# 06_FPGA_B.net
KiCad netlist of a schematic drawn in Altium Designer
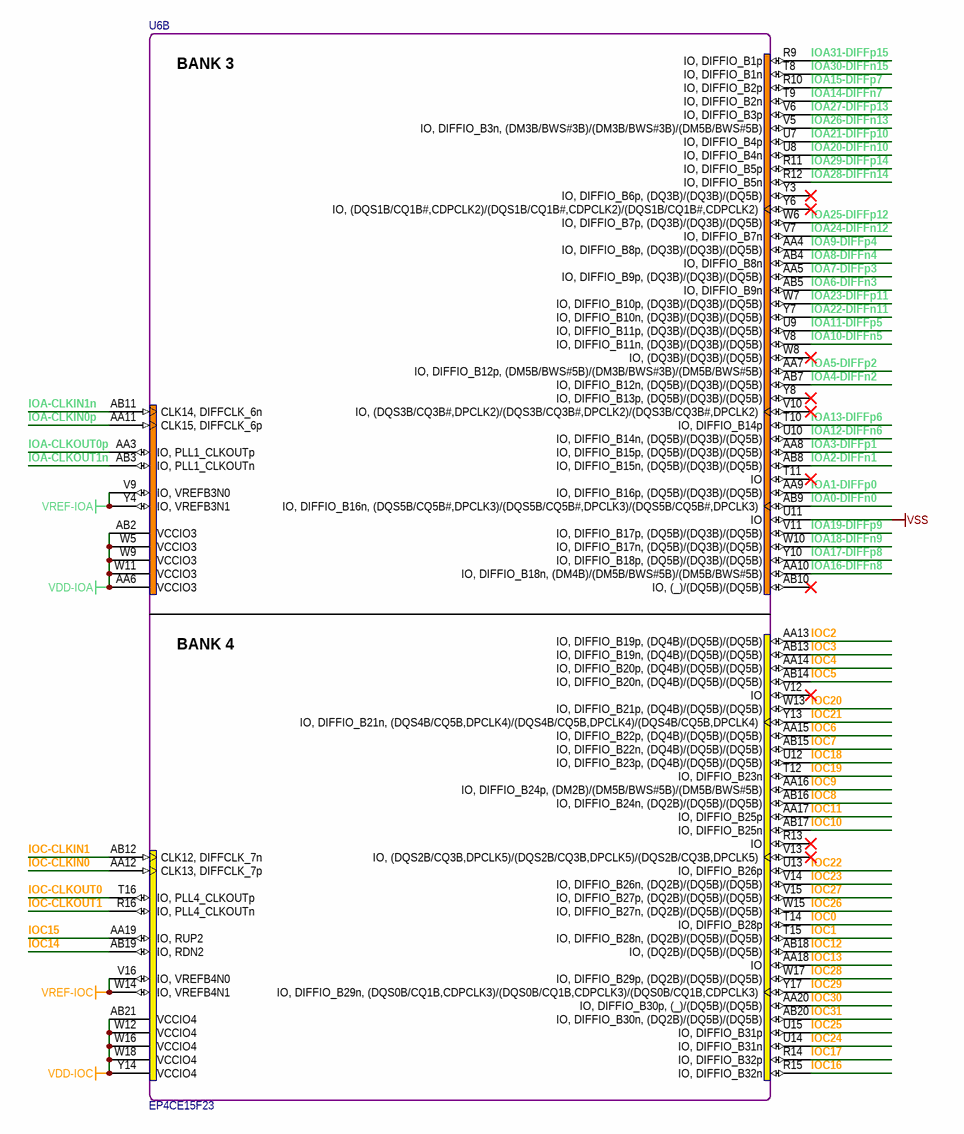
[diagram p0: 06_FPGA_B.SchDoc]

(export (version "E")
  (design (tool "Eeschema 10.0.6"))
  (components
    (comp (ref "U6")
      (value "EP4CE15F23")
      (footprint "FBGA-484")
      (description "Cyclone IV EP4CE15F23 FPGA")
      (fields
        (field (name "PARTNUMBER") "EP4CE15F23C8N")
        (field (name "DESIGNER") "shyul")
        (field (name "PUBLISHER") "Cowin")
      )
      (libsource (lib "PCB_XEM-S91") (part "EP4CE15F23"))
    )
  )
  (nets
    (net (code "1") (name "/IOA-CLKIN0p") (class "Default")
      (node (ref "U6") (pin "AA11") (pinfunction "CLK15,_DIFFCLK_6p_AA11") (pintype "input"))
    )
    (net (code "2") (name "/IOA-CLKIN1n") (class "Default")
      (node (ref "U6") (pin "AB11") (pinfunction "CLK14,_DIFFCLK_6n_AB11") (pintype "input"))
    )
    (net (code "3") (name "/IOA-CLKOUT0p") (class "Default")
      (node (ref "U6") (pin "AA3") (pinfunction "IO,_PLL1_CLKOUTp_AA3") (pintype "bidirectional"))
    )
    (net (code "4") (name "/IOA-CLKOUT1n") (class "Default")
      (node (ref "U6") (pin "AB3") (pinfunction "IO,_PLL1_CLKOUTn_AB3") (pintype "bidirectional"))
    )
    (net (code "5") (name "/IOA0-DIFFn0") (class "Default")
      (node (ref "U6") (pin "AB9") (pinfunction "IO,_DIFFIO_B16n,_(DQS5B/CQ5B#,DPCLK3)/(DQS5B/CQ5B#,DPCLK3)/(DQS5B/CQ5B#,DPCLK3)_AB9") (pintype "bidirectional"))
    )
    (net (code "6") (name "/IOA1-DIFFp0") (class "Default")
      (node (ref "U6") (pin "AA9") (pinfunction "IO,_DIFFIO_B16p,_(DQ5B)/(DQ3B)/(DQ5B)_AA9") (pintype "bidirectional"))
    )
    (net (code "7") (name "/IOA2-DIFFn1") (class "Default")
      (node (ref "U6") (pin "AB8") (pinfunction "IO,_DIFFIO_B15n,_(DQ5B)/(DQ3B)/(DQ5B)_AB8") (pintype "bidirectional"))
    )
    (net (code "8") (name "/IOA3-DIFFp1") (class "Default")
      (node (ref "U6") (pin "AA8") (pinfunction "IO,_DIFFIO_B15p,_(DQ5B)/(DQ3B)/(DQ5B)_AA8") (pintype "bidirectional"))
    )
    (net (code "9") (name "/IOA4-DIFFn2") (class "Default")
      (node (ref "U6") (pin "AB7") (pinfunction "IO,_DIFFIO_B12n,_(DQ5B)/(DQ3B)/(DQ5B)_AB7") (pintype "bidirectional"))
    )
    (net (code "10") (name "/IOA5-DIFFp2") (class "Default")
      (node (ref "U6") (pin "AA7") (pinfunction "IO,_DIFFIO_B12p,_(DM5B/BWS#5B)/(DM3B/BWS#3B)/(DM5B/BWS#5B)_AA7") (pintype "bidirectional"))
    )
    (net (code "11") (name "/IOA6-DIFFn3") (class "Default")
      (node (ref "U6") (pin "AB5") (pinfunction "IO,_DIFFIO_B9n_AB5") (pintype "bidirectional"))
    )
    (net (code "12") (name "/IOA7-DIFFp3") (class "Default")
      (node (ref "U6") (pin "AA5") (pinfunction "IO,_DIFFIO_B9p,_(DQ3B)/(DQ3B)/(DQ5B)_AA5") (pintype "bidirectional"))
    )
    (net (code "13") (name "/IOA8-DIFFn4") (class "Default")
      (node (ref "U6") (pin "AB4") (pinfunction "IO,_DIFFIO_B8n_AB4") (pintype "bidirectional"))
    )
    (net (code "14") (name "/IOA9-DIFFp4") (class "Default")
      (node (ref "U6") (pin "AA4") (pinfunction "IO,_DIFFIO_B8p,_(DQ3B)/(DQ3B)/(DQ5B)_AA4") (pintype "bidirectional"))
    )
    (net (code "15") (name "/IOA10-DIFFn5") (class "Default")
      (node (ref "U6") (pin "V8") (pinfunction "IO,_DIFFIO_B11n,_(DQ3B)/(DQ3B)/(DQ5B)_V8") (pintype "bidirectional"))
    )
    (net (code "16") (name "/IOA11-DIFFp5") (class "Default")
      (node (ref "U6") (pin "U9") (pinfunction "IO,_DIFFIO_B11p,_(DQ3B)/(DQ3B)/(DQ5B)_U9") (pintype "bidirectional"))
    )
    (net (code "17") (name "/IOA12-DIFFn6") (class "Default")
      (node (ref "U6") (pin "U10") (pinfunction "IO,_DIFFIO_B14n,_(DQ5B)/(DQ3B)/(DQ5B)_U10") (pintype "bidirectional"))
    )
    (net (code "18") (name "/IOA13-DIFFp6") (class "Default")
      (node (ref "U6") (pin "T10") (pinfunction "IO,_DIFFIO_B14p_T10") (pintype "bidirectional"))
    )
    (net (code "19") (name "/IOA14-DIFFn7") (class "Default")
      (node (ref "U6") (pin "T9") (pinfunction "IO,_DIFFIO_B2n_T9") (pintype "bidirectional"))
    )
    (net (code "20") (name "/IOA15-DIFFp7") (class "Default")
      (node (ref "U6") (pin "R10") (pinfunction "IO,_DIFFIO_B2p_R10") (pintype "bidirectional"))
    )
    (net (code "21") (name "/IOA16-DIFFn8") (class "Default")
      (node (ref "U6") (pin "AA10") (pinfunction "IO,_DIFFIO_B18n,_(DM4B)/(DM5B/BWS#5B)/(DM5B/BWS#5B)_AA10") (pintype "bidirectional"))
    )
    (net (code "22") (name "/IOA17-DIFFp8") (class "Default")
      (node (ref "U6") (pin "Y10") (pinfunction "IO,_DIFFIO_B18p,_(DQ5B)/(DQ3B)/(DQ5B)_Y10") (pintype "bidirectional"))
    )
    (net (code "23") (name "/IOA18-DIFFn9") (class "Default")
      (node (ref "U6") (pin "W10") (pinfunction "IO,_DIFFIO_B17n,_(DQ5B)/(DQ3B)/(DQ5B)_W10") (pintype "bidirectional"))
    )
    (net (code "24") (name "/IOA19-DIFFp9") (class "Default")
      (node (ref "U6") (pin "V11") (pinfunction "IO,_DIFFIO_B17p,_(DQ5B)/(DQ3B)/(DQ5B)_V11") (pintype "bidirectional"))
    )
    (net (code "25") (name "/IOA20-DIFFn10") (class "Default")
      (node (ref "U6") (pin "U8") (pinfunction "IO,_DIFFIO_B4n_U8") (pintype "bidirectional"))
    )
    (net (code "26") (name "/IOA21-DIFFp10") (class "Default")
      (node (ref "U6") (pin "U7") (pinfunction "IO,_DIFFIO_B4p_U7") (pintype "bidirectional"))
    )
    (net (code "27") (name "/IOA22-DIFFn11") (class "Default")
      (node (ref "U6") (pin "Y7") (pinfunction "IO,_DIFFIO_B10n,_(DQ3B)/(DQ3B)/(DQ5B)_Y7") (pintype "bidirectional"))
    )
    (net (code "28") (name "/IOA23-DIFFp11") (class "Default")
      (node (ref "U6") (pin "W7") (pinfunction "IO,_DIFFIO_B10p,_(DQ3B)/(DQ3B)/(DQ5B)_W7") (pintype "bidirectional"))
    )
    (net (code "29") (name "/IOA24-DIFFn12") (class "Default")
      (node (ref "U6") (pin "V7") (pinfunction "IO,_DIFFIO_B7n_V7") (pintype "bidirectional"))
    )
    (net (code "30") (name "/IOA25-DIFFp12") (class "Default")
      (node (ref "U6") (pin "W6") (pinfunction "IO,_DIFFIO_B7p,_(DQ3B)/(DQ3B)/(DQ5B)_W6") (pintype "bidirectional"))
    )
    (net (code "31") (name "/IOA26-DIFFn13") (class "Default")
      (node (ref "U6") (pin "V5") (pinfunction "IO,_DIFFIO_B3n,_(DM3B/BWS#3B)/(DM3B/BWS#3B)/(DM5B/BWS#5B)_V5") (pintype "bidirectional"))
    )
    (net (code "32") (name "/IOA27-DIFFp13") (class "Default")
      (node (ref "U6") (pin "V6") (pinfunction "IO,_DIFFIO_B3p_V6") (pintype "bidirectional"))
    )
    (net (code "33") (name "/IOA28-DIFFn14") (class "Default")
      (node (ref "U6") (pin "R12") (pinfunction "IO,_DIFFIO_B5n_R12") (pintype "bidirectional"))
    )
    (net (code "34") (name "/IOA29-DIFFp14") (class "Default")
      (node (ref "U6") (pin "R11") (pinfunction "IO,_DIFFIO_B5p_R11") (pintype "bidirectional"))
    )
    (net (code "35") (name "/IOA30-DIFFn15") (class "Default")
      (node (ref "U6") (pin "T8") (pinfunction "IO,_DIFFIO_B1n_T8") (pintype "bidirectional"))
    )
    (net (code "36") (name "/IOA31-DIFFp15") (class "Default")
      (node (ref "U6") (pin "R9") (pinfunction "IO,_DIFFIO_B1p_R9") (pintype "bidirectional"))
    )
    (net (code "37") (name "/IOC-CLKIN0") (class "Default")
      (node (ref "U6") (pin "AA12") (pinfunction "CLK13,_DIFFCLK_7p_AA12") (pintype "input"))
    )
    (net (code "38") (name "/IOC-CLKIN1") (class "Default")
      (node (ref "U6") (pin "AB12") (pinfunction "CLK12,_DIFFCLK_7n_AB12") (pintype "input"))
    )
    (net (code "39") (name "/IOC-CLKOUT0") (class "Default")
      (node (ref "U6") (pin "T16") (pinfunction "IO,_PLL4_CLKOUTp_T16") (pintype "bidirectional"))
    )
    (net (code "40") (name "/IOC-CLKOUT1") (class "Default")
      (node (ref "U6") (pin "R16") (pinfunction "IO,_PLL4_CLKOUTn_R16") (pintype "bidirectional"))
    )
    (net (code "41") (name "/IOC0") (class "Default")
      (node (ref "U6") (pin "T14") (pinfunction "IO,_DIFFIO_B28p_T14") (pintype "bidirectional"))
    )
    (net (code "42") (name "/IOC1") (class "Default")
      (node (ref "U6") (pin "T15") (pinfunction "IO,_DIFFIO_B28n,_(DQ2B)/(DQ5B)/(DQ5B)_T15") (pintype "bidirectional"))
    )
    (net (code "43") (name "/IOC2") (class "Default")
      (node (ref "U6") (pin "AA13") (pinfunction "IO,_DIFFIO_B19p,_(DQ4B)/(DQ5B)/(DQ5B)_AA13") (pintype "bidirectional"))
    )
    (net (code "44") (name "/IOC3") (class "Default")
      (node (ref "U6") (pin "AB13") (pinfunction "IO,_DIFFIO_B19n,_(DQ4B)/(DQ5B)/(DQ5B)_AB13") (pintype "bidirectional"))
    )
    (net (code "45") (name "/IOC4") (class "Default")
      (node (ref "U6") (pin "AA14") (pinfunction "IO,_DIFFIO_B20p,_(DQ4B)/(DQ5B)/(DQ5B)_AA14") (pintype "bidirectional"))
    )
    (net (code "46") (name "/IOC5") (class "Default")
      (node (ref "U6") (pin "AB14") (pinfunction "IO,_DIFFIO_B20n,_(DQ4B)/(DQ5B)/(DQ5B)_AB14") (pintype "bidirectional"))
    )
    (net (code "47") (name "/IOC6") (class "Default")
      (node (ref "U6") (pin "AA15") (pinfunction "IO,_DIFFIO_B22p,_(DQ4B)/(DQ5B)/(DQ5B)_AA15") (pintype "bidirectional"))
    )
    (net (code "48") (name "/IOC7") (class "Default")
      (node (ref "U6") (pin "AB15") (pinfunction "IO,_DIFFIO_B22n,_(DQ4B)/(DQ5B)/(DQ5B)_AB15") (pintype "bidirectional"))
    )
    (net (code "49") (name "/IOC8") (class "Default")
      (node (ref "U6") (pin "AB16") (pinfunction "IO,_DIFFIO_B24n,_(DQ2B)/(DQ5B)/(DQ5B)_AB16") (pintype "bidirectional"))
    )
    (net (code "50") (name "/IOC9") (class "Default")
      (node (ref "U6") (pin "AA16") (pinfunction "IO,_DIFFIO_B24p,_(DM2B)/(DM5B/BWS#5B)/(DM5B/BWS#5B)_AA16") (pintype "bidirectional"))
    )
    (net (code "51") (name "/IOC10") (class "Default")
      (node (ref "U6") (pin "AB17") (pinfunction "IO,_DIFFIO_B25n_AB17") (pintype "bidirectional"))
    )
    (net (code "52") (name "/IOC11") (class "Default")
      (node (ref "U6") (pin "AA17") (pinfunction "IO,_DIFFIO_B25p_AA17") (pintype "bidirectional"))
    )
    (net (code "53") (name "/IOC12") (class "Default")
      (node (ref "U6") (pin "AB18") (pinfunction "IO,_(DQ2B)/(DQ5B)/(DQ5B)_AB18") (pintype "bidirectional"))
    )
    (net (code "54") (name "/IOC13") (class "Default")
      (node (ref "U6") (pin "AA18") (pinfunction "IO_AA18") (pintype "bidirectional"))
    )
    (net (code "55") (name "/IOC14") (class "Default")
      (node (ref "U6") (pin "AB19") (pinfunction "IO,_RDN2_AB19") (pintype "bidirectional"))
    )
    (net (code "56") (name "/IOC15") (class "Default")
      (node (ref "U6") (pin "AA19") (pinfunction "IO,_RUP2_AA19") (pintype "bidirectional"))
    )
    (net (code "57") (name "/IOC16") (class "Default")
      (node (ref "U6") (pin "R15") (pinfunction "IO,_DIFFIO_B32n_R15") (pintype "bidirectional"))
    )
    (net (code "58") (name "/IOC17") (class "Default")
      (node (ref "U6") (pin "R14") (pinfunction "IO,_DIFFIO_B32p_R14") (pintype "bidirectional"))
    )
    (net (code "59") (name "/IOC18") (class "Default")
      (node (ref "U6") (pin "U12") (pinfunction "IO,_DIFFIO_B23p,_(DQ4B)/(DQ5B)/(DQ5B)_U12") (pintype "bidirectional"))
    )
    (net (code "60") (name "/IOC19") (class "Default")
      (node (ref "U6") (pin "T12") (pinfunction "IO,_DIFFIO_B23n_T12") (pintype "bidirectional"))
    )
    (net (code "61") (name "/IOC20") (class "Default")
      (node (ref "U6") (pin "W13") (pinfunction "IO,_DIFFIO_B21p,_(DQ4B)/(DQ5B)/(DQ5B)_W13") (pintype "bidirectional"))
    )
    (net (code "62") (name "/IOC21") (class "Default")
      (node (ref "U6") (pin "Y13") (pinfunction "IO,_DIFFIO_B21n,_(DQS4B/CQ5B,DPCLK4)/(DQS4B/CQ5B,DPCLK4)/(DQS4B/CQ5B,DPCLK4)_Y13") (pintype "bidirectional"))
    )
    (net (code "63") (name "/IOC22") (class "Default")
      (node (ref "U6") (pin "U13") (pinfunction "IO,_DIFFIO_B26p_U13") (pintype "bidirectional"))
    )
    (net (code "64") (name "/IOC23") (class "Default")
      (node (ref "U6") (pin "V14") (pinfunction "IO,_DIFFIO_B26n,_(DQ2B)/(DQ5B)/(DQ5B)_V14") (pintype "bidirectional"))
    )
    (net (code "65") (name "/IOC24") (class "Default")
      (node (ref "U6") (pin "U14") (pinfunction "IO,_DIFFIO_B31n_U14") (pintype "bidirectional"))
    )
    (net (code "66") (name "/IOC25") (class "Default")
      (node (ref "U6") (pin "U15") (pinfunction "IO,_DIFFIO_B31p_U15") (pintype "bidirectional"))
    )
    (net (code "67") (name "/IOC26") (class "Default")
      (node (ref "U6") (pin "W15") (pinfunction "IO,_DIFFIO_B27n,_(DQ2B)/(DQ5B)/(DQ5B)_W15") (pintype "bidirectional"))
    )
    (net (code "68") (name "/IOC27") (class "Default")
      (node (ref "U6") (pin "V15") (pinfunction "IO,_DIFFIO_B27p,_(DQ2B)/(DQ5B)/(DQ5B)_V15") (pintype "bidirectional"))
    )
    (net (code "69") (name "/IOC28") (class "Default")
      (node (ref "U6") (pin "W17") (pinfunction "IO,_DIFFIO_B29p,_(DQ2B)/(DQ5B)/(DQ5B)_W17") (pintype "bidirectional"))
    )
    (net (code "70") (name "/IOC29") (class "Default")
      (node (ref "U6") (pin "Y17") (pinfunction "IO,_DIFFIO_B29n,_(DQS0B/CQ1B,CDPCLK3)/(DQS0B/CQ1B,CDPCLK3)/(DQS0B/CQ1B,CDPCLK3)_Y17") (pintype "bidirectional"))
    )
    (net (code "71") (name "/IOC30") (class "Default")
      (node (ref "U6") (pin "AA20") (pinfunction "IO,_DIFFIO_B30p,_(_)/(DQ5B)/(DQ5B)_AA20") (pintype "bidirectional"))
    )
    (net (code "72") (name "/IOC31") (class "Default")
      (node (ref "U6") (pin "AB20") (pinfunction "IO,_DIFFIO_B30n,_(DQ2B)/(DQ5B)/(DQ5B)_AB20") (pintype "bidirectional"))
    )
    (net (code "73") (name "VDD-IOA") (class "Default")
      (node (ref "U6") (pin "AA6") (pinfunction "VCCIO3_AA6") (pintype "power_in"))
      (node (ref "U6") (pin "AB2") (pinfunction "VCCIO3_AB2") (pintype "power_in"))
      (node (ref "U6") (pin "W11") (pinfunction "VCCIO3_W11") (pintype "power_in"))
      (node (ref "U6") (pin "W5") (pinfunction "VCCIO3_W5") (pintype "power_in"))
      (node (ref "U6") (pin "W9") (pinfunction "VCCIO3_W9") (pintype "power_in"))
    )
    (net (code "74") (name "VDD-IOC") (class "Default")
      (node (ref "U6") (pin "AB21") (pinfunction "VCCIO4_AB21") (pintype "power_in"))
      (node (ref "U6") (pin "W12") (pinfunction "VCCIO4_W12") (pintype "power_in"))
      (node (ref "U6") (pin "W16") (pinfunction "VCCIO4_W16") (pintype "power_in"))
      (node (ref "U6") (pin "W18") (pinfunction "VCCIO4_W18") (pintype "power_in"))
      (node (ref "U6") (pin "Y14") (pinfunction "VCCIO4_Y14") (pintype "power_in"))
    )
    (net (code "75") (name "VREF-IOA") (class "Default")
      (node (ref "U6") (pin "V9") (pinfunction "IO,_VREFB3N0_V9") (pintype "bidirectional"))
      (node (ref "U6") (pin "Y4") (pinfunction "IO,_VREFB3N1_Y4") (pintype "bidirectional"))
    )
    (net (code "76") (name "VREF-IOC") (class "Default")
      (node (ref "U6") (pin "V16") (pinfunction "IO,_VREFB4N0_V16") (pintype "bidirectional"))
      (node (ref "U6") (pin "W14") (pinfunction "IO,_VREFB4N1_W14") (pintype "bidirectional"))
    )
    (net (code "77") (name "VSS") (class "Default")
      (node (ref "U6") (pin "U11") (pinfunction "IO_U11") (pintype "bidirectional"))
    )
    (net (code "78") (name "unconnected-(U6B-IO,_(DQ3B){slash}(DQ3B){slash}(DQ5B)-PadW8)") (class "Default")
      (node (ref "U6") (pin "W8") (pinfunction "IO,_(DQ3B)/(DQ3B)/(DQ5B)_W8") (pintype "bidirectional+no_connect"))
    )
    (net (code "79") (name "unconnected-(U6B-IO,_(DQS1B{slash}CQ1B#,CDPCLK2){slash}(DQS1B{slash}CQ1B#,CDPCLK2){slash}(DQS1B{slash}CQ1B#,CDPCLK2)-PadY6)") (class "Default")
      (node (ref "U6") (pin "Y6") (pinfunction "IO,_(DQS1B/CQ1B#,CDPCLK2)/(DQS1B/CQ1B#,CDPCLK2)/(DQS1B/CQ1B#,CDPCLK2)_Y6") (pintype "bidirectional+no_connect"))
    )
    (net (code "80") (name "unconnected-(U6B-IO,_(DQS2B{slash}CQ3B,DPCLK5){slash}(DQS2B{slash}CQ3B,DPCLK5){slash}(DQS2B{slash}CQ3B,DPCLK5)-PadV13)") (class "Default")
      (node (ref "U6") (pin "V13") (pinfunction "IO,_(DQS2B/CQ3B,DPCLK5)/(DQS2B/CQ3B,DPCLK5)/(DQS2B/CQ3B,DPCLK5)_V13") (pintype "bidirectional+no_connect"))
    )
    (net (code "81") (name "unconnected-(U6B-IO,_(DQS3B{slash}CQ3B#,DPCLK2){slash}(DQS3B{slash}CQ3B#,DPCLK2){slash}(DQS3B{slash}CQ3B#,DPCLK2)-PadV10)") (class "Default")
      (node (ref "U6") (pin "V10") (pinfunction "IO,_(DQS3B/CQ3B#,DPCLK2)/(DQS3B/CQ3B#,DPCLK2)/(DQS3B/CQ3B#,DPCLK2)_V10") (pintype "bidirectional+no_connect"))
    )
    (net (code "82") (name "unconnected-(U6B-IO,_(_){slash}(DQ5B){slash}(DQ5B)-PadAB10)") (class "Default")
      (node (ref "U6") (pin "AB10") (pinfunction "IO,_(_)/(DQ5B)/(DQ5B)_AB10") (pintype "bidirectional+no_connect"))
    )
    (net (code "83") (name "unconnected-(U6B-IO,_DIFFIO_B6p,_(DQ3B){slash}(DQ3B){slash}(DQ5B)-PadY3)") (class "Default")
      (node (ref "U6") (pin "Y3") (pinfunction "IO,_DIFFIO_B6p,_(DQ3B)/(DQ3B)/(DQ5B)_Y3") (pintype "bidirectional+no_connect"))
    )
    (net (code "84") (name "unconnected-(U6B-IO,_DIFFIO_B13p,_(DQ5B){slash}(DQ3B){slash}(DQ5B)-PadY8)") (class "Default")
      (node (ref "U6") (pin "Y8") (pinfunction "IO,_DIFFIO_B13p,_(DQ5B)/(DQ3B)/(DQ5B)_Y8") (pintype "bidirectional+no_connect"))
    )
    (net (code "85") (name "unconnected-(U6B-IO-PadR13)") (class "Default")
      (node (ref "U6") (pin "R13") (pinfunction "IO_R13") (pintype "bidirectional+no_connect"))
    )
    (net (code "86") (name "unconnected-(U6B-IO-PadT11)") (class "Default")
      (node (ref "U6") (pin "T11") (pinfunction "IO_T11") (pintype "bidirectional+no_connect"))
    )
    (net (code "87") (name "unconnected-(U6B-IO-PadV12)") (class "Default")
      (node (ref "U6") (pin "V12") (pinfunction "IO_V12") (pintype "bidirectional+no_connect"))
    )
  )
)
